# Main.net
KiCad netlist of a schematic drawn in Altium Designer
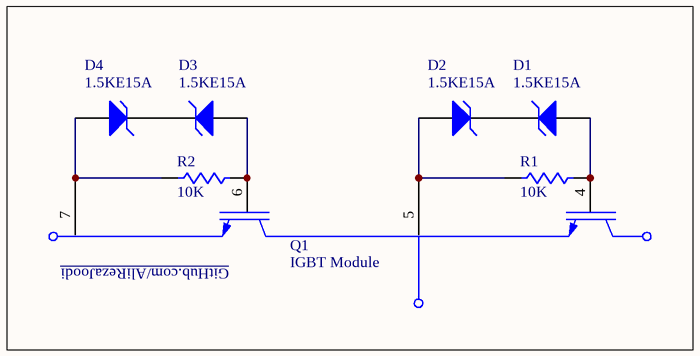
[diagram p0: Main.SchDoc]

(export (version "E")
  (design (tool "Eeschema 10.0.6"))
  (components
    (comp (ref "D1")
      (value "1.5KE15A")
      (footprint "DIODE0.7V_number")
      (description "Zener Diode")
      (fields (field (name "MANUFACTURER") "Generic Components") (field (name "PUBLISHER") "Altium Limited"))
      (libsource (lib "Miscellaneous Devices") (part "D Zener"))
    )
    (comp (ref "D2")
      (value "1.5KE15A")
      (footprint "DIODE0.7V_number")
      (description "Zener Diode")
      (fields (field (name "MANUFACTURER") "Generic Components") (field (name "PUBLISHER") "Altium Limited"))
      (libsource (lib "Miscellaneous Devices") (part "D Zener"))
    )
    (comp (ref "D3")
      (value "1.5KE15A")
      (footprint "DIODE0.7V_N")
      (description "Zener Diode")
      (fields (field (name "MANUFACTURER") "Generic Components") (field (name "PUBLISHER") "Altium Limited"))
      (libsource (lib "Miscellaneous Devices") (part "D Zener"))
    )
    (comp (ref "D4")
      (value "1.5KE15A")
      (footprint "DIODE0.7V_N")
      (description "Zener Diode")
      (fields (field (name "MANUFACTURER") "Generic Components") (field (name "PUBLISHER") "Altium Limited"))
      (libsource (lib "Miscellaneous Devices") (part "D Zener"))
    )
    (comp (ref "Q1")
      (value "IGBT Module")
      (footprint "IGBT_Power")
      (description "N-Channel MOSFET")
      (fields (field (name "MANUFACTURER") "Generic Components") (field (name "PUBLISHER") "Altium Limited"))
      (libsource (lib "my Libraries") (part "IGBT_Power"))
    )
    (comp (ref "R1")
      (value "10K")
      (footprint "0805")
      (description "Resistor")
      (fields (field (name "MANUFACTURER") "Generic Components") (field (name "PUBLISHER") "Altium Limited"))
      (libsource (lib "Miscellaneous Devices") (part "Res1"))
    )
    (comp (ref "R2")
      (value "10K")
      (footprint "0805")
      (description "Resistor")
      (fields (field (name "MANUFACTURER") "Generic Components") (field (name "PUBLISHER") "Altium Limited"))
      (libsource (lib "Miscellaneous Devices") (part "Res1"))
    )
  )
  (nets
    (net (code "1") (name "Net-(D1-A)") (class "Default")
      (node (ref "D1") (pin "1") (pinfunction "A_1") (pintype "passive"))
      (node (ref "Q1") (pin "4") (pinfunction "G_4") (pintype "passive"))
      (node (ref "R1") (pin "2") (pinfunction "2_2") (pintype "passive"))
    )
    (net (code "2") (name "Net-(D1-K)") (class "Default")
      (node (ref "D1") (pin "2") (pinfunction "K_2") (pintype "passive"))
      (node (ref "D2") (pin "2") (pinfunction "K_2") (pintype "passive"))
    )
    (net (code "3") (name "Net-(D2-A)") (class "Default")
      (node (ref "D2") (pin "1") (pinfunction "A_1") (pintype "passive"))
      (node (ref "Q1") (pin "5") (pinfunction "S_5") (pintype "passive"))
      (node (ref "R1") (pin "1") (pinfunction "1_1") (pintype "passive"))
    )
    (net (code "4") (name "Net-(D3-A)") (class "Default")
      (node (ref "D3") (pin "1") (pinfunction "A_1") (pintype "passive"))
      (node (ref "Q1") (pin "6") (pinfunction "G_6") (pintype "passive"))
      (node (ref "R2") (pin "2") (pinfunction "2_2") (pintype "passive"))
    )
    (net (code "5") (name "Net-(D3-K)") (class "Default")
      (node (ref "D3") (pin "2") (pinfunction "K_2") (pintype "passive"))
      (node (ref "D4") (pin "2") (pinfunction "K_2") (pintype "passive"))
    )
    (net (code "6") (name "Net-(D4-A)") (class "Default")
      (node (ref "D4") (pin "1") (pinfunction "A_1") (pintype "passive"))
      (node (ref "Q1") (pin "7") (pinfunction "S_7") (pintype "passive"))
      (node (ref "R2") (pin "1") (pinfunction "1_1") (pintype "passive"))
    )
  )
)
